# LCD_PWR.net
KiCad netlist of a schematic drawn in Altium Designer
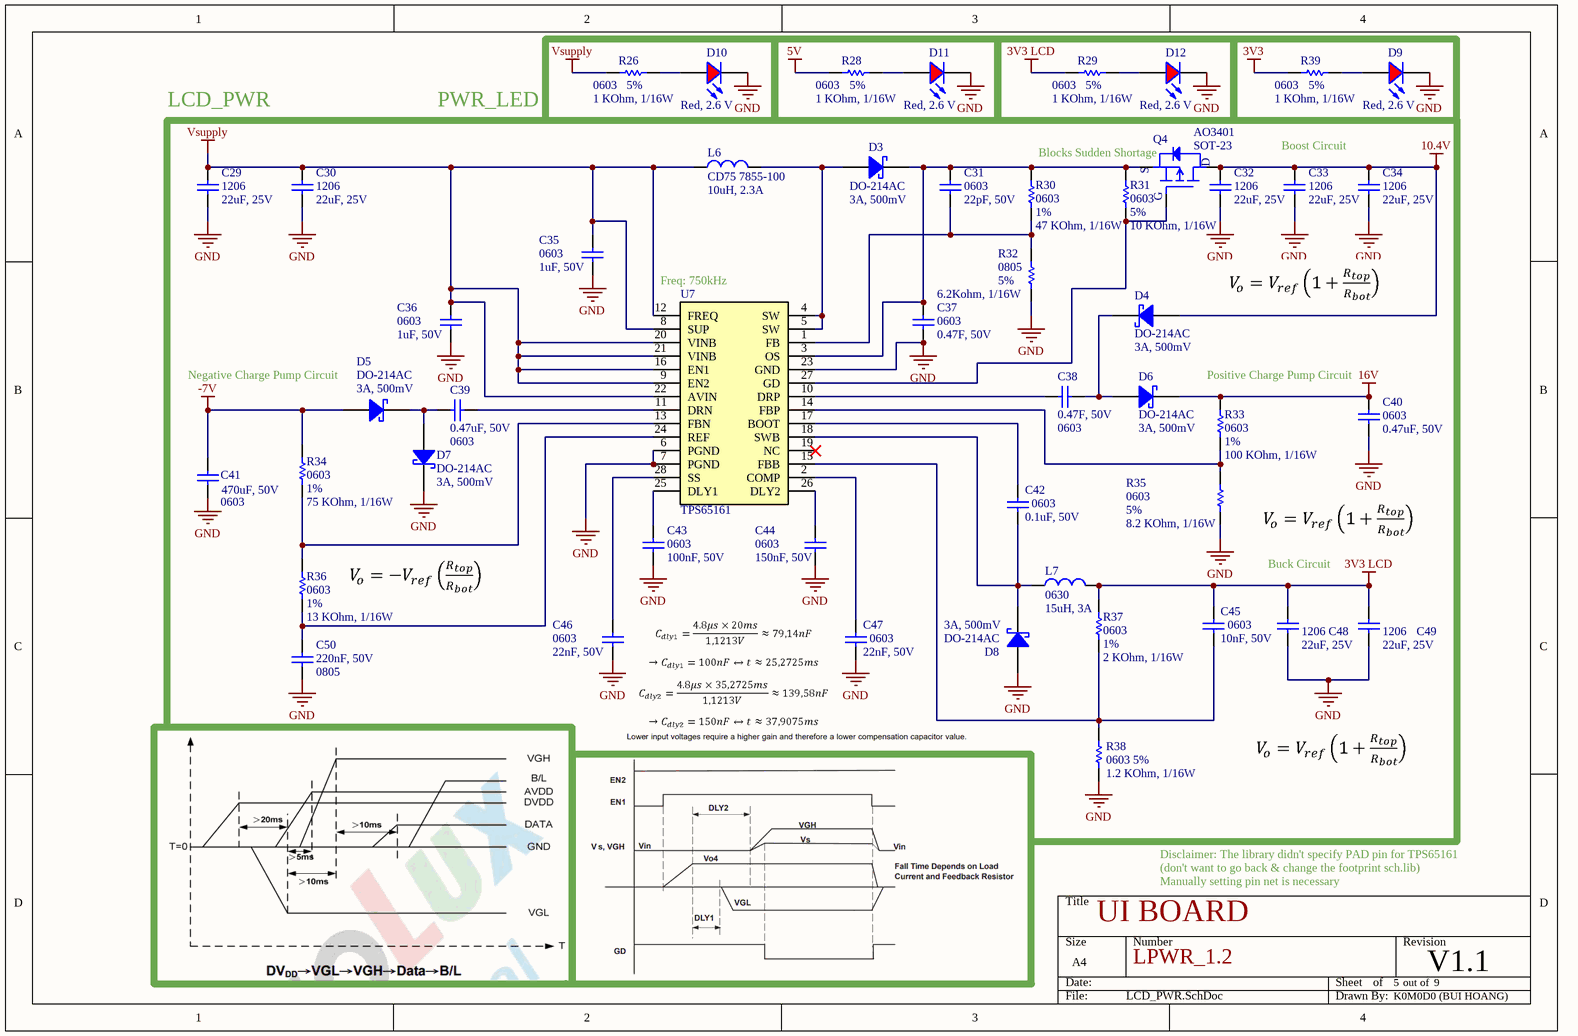
[diagram p0: LCD_PWR.SchDoc]

(export (version "E")
  (design (tool "Eeschema 10.0.6"))
  (components
    (comp (ref "C29")
      (value "22uF, 25V")
      (footprint "C_1206")
      (description "CAP_1206")
      (fields (field (name "PACKAGE") "1206"))
      (libsource (lib "DisplayLib") (part "CAP_1206"))
    )
    (comp (ref "C30")
      (value "22uF, 25V")
      (footprint "C_1206")
      (description "CAP_1206")
      (fields (field (name "PACKAGE") "1206"))
      (libsource (lib "DisplayLib") (part "CAP_1206"))
    )
    (comp (ref "C31")
      (value "22pF, 50V")
      (footprint "C_0603")
      (description "CAP_0603")
      (fields (field (name "PACKAGE") "0603"))
      (libsource (lib "DisplayLib") (part "CAP_0603"))
    )
    (comp (ref "C32")
      (value "22uF, 25V")
      (footprint "C_1206")
      (description "CAP_1206")
      (fields (field (name "PACKAGE") "1206"))
      (libsource (lib "DisplayLib") (part "CAP_1206"))
    )
    (comp (ref "C33")
      (value "22uF, 25V")
      (footprint "C_1206")
      (description "CAP_1206")
      (fields (field (name "PACKAGE") "1206"))
      (libsource (lib "DisplayLib") (part "CAP_1206"))
    )
    (comp (ref "C34")
      (value "22uF, 25V")
      (footprint "C_1206")
      (description "CAP_1206")
      (fields (field (name "PACKAGE") "1206"))
      (libsource (lib "DisplayLib") (part "CAP_1206"))
    )
    (comp (ref "C35")
      (value "1uF, 50V")
      (footprint "C_0603")
      (description "CAP_0603")
      (fields (field (name "PACKAGE") "0603"))
      (libsource (lib "DisplayLib") (part "CAP_0603"))
    )
    (comp (ref "C36")
      (value "1uF, 50V")
      (footprint "C_0603")
      (description "CAP_0603")
      (fields (field (name "PACKAGE") "0603"))
      (libsource (lib "DisplayLib") (part "CAP_0603"))
    )
    (comp (ref "C37")
      (value "0.47F, 50V")
      (footprint "C_0603")
      (description "CAP_0603")
      (fields (field (name "PACKAGE") "0603"))
      (libsource (lib "DisplayLib") (part "CAP_0603"))
    )
    (comp (ref "C38")
      (value "0.47F, 50V")
      (footprint "C_0603")
      (description "CAP_0603")
      (fields (field (name "PACKAGE") "0603"))
      (libsource (lib "DisplayLib") (part "CAP_0603"))
    )
    (comp (ref "C39")
      (value "0.47uF, 50V")
      (footprint "C_0603")
      (description "CAP_0603")
      (fields (field (name "PACKAGE") "0603"))
      (libsource (lib "DisplayLib") (part "CAP_0603"))
    )
    (comp (ref "C40")
      (value "0.47uF, 50V")
      (footprint "C_0603")
      (description "CAP_0603")
      (fields (field (name "PACKAGE") "0603"))
      (libsource (lib "DisplayLib") (part "CAP_0603"))
    )
    (comp (ref "C41")
      (value "470uF, 50V")
      (footprint "C_0603")
      (description "CAP_0603")
      (fields (field (name "PACKAGE") "0603"))
      (libsource (lib "DisplayLib") (part "CAP_0603"))
    )
    (comp (ref "C42")
      (value "0.1uF, 50V")
      (footprint "C_0603")
      (description "CAP_0603")
      (fields (field (name "PACKAGE") "0603"))
      (libsource (lib "DisplayLib") (part "CAP_0603"))
    )
    (comp (ref "C43")
      (value "100nF, 50V")
      (footprint "C_0603")
      (description "CAP_0603")
      (fields (field (name "PACKAGE") "0603"))
      (libsource (lib "DisplayLib") (part "CAP_0603"))
    )
    (comp (ref "C44")
      (value "150nF, 50V")
      (footprint "C_0603")
      (description "CAP_0603")
      (fields (field (name "PACKAGE") "0603"))
      (libsource (lib "DisplayLib") (part "CAP_0603"))
    )
    (comp (ref "C45")
      (value "10nF, 50V")
      (footprint "C_0603")
      (description "CAP_0603")
      (fields (field (name "PACKAGE") "0603"))
      (libsource (lib "DisplayLib") (part "CAP_0603"))
    )
    (comp (ref "C46")
      (value "22nF, 50V")
      (footprint "C_0603")
      (description "CAP_0603")
      (fields (field (name "PACKAGE") "0603"))
      (libsource (lib "DisplayLib") (part "CAP_0603"))
    )
    (comp (ref "C47")
      (value "22nF, 50V")
      (footprint "C_0603")
      (description "CAP_0603")
      (fields (field (name "PACKAGE") "0603"))
      (libsource (lib "DisplayLib") (part "CAP_0603"))
    )
    (comp (ref "C48")
      (value "22uF, 25V")
      (footprint "C_1206")
      (description "CAP_1206")
      (fields (field (name "PACKAGE") "1206"))
      (libsource (lib "DisplayLib") (part "CAP_1206"))
    )
    (comp (ref "C49")
      (value "22uF, 25V")
      (footprint "C_1206")
      (description "CAP_1206")
      (fields (field (name "PACKAGE") "1206"))
      (libsource (lib "DisplayLib") (part "CAP_1206"))
    )
    (comp (ref "C50")
      (value "220nF, 50V")
      (footprint "C_0805")
      (description "CAP_0805")
      (fields (field (name "PACKAGE") "0805"))
      (libsource (lib "DisplayLib") (part "CAP_0805"))
    )
    (comp (ref "D3")
      (value "3A, 500mV")
      (footprint "PKG_SMA (DO-214AC)")
      (description "SS34")
      (fields (field (name "PACKAGE") "DO-214AC"))
      (libsource (lib "DisplayLib") (part "SCHOTTKY"))
    )
    (comp (ref "D4")
      (value "3A, 500mV")
      (footprint "PKG_SMA (DO-214AC)")
      (description "SS34")
      (fields (field (name "PACKAGE") "DO-214AC"))
      (libsource (lib "DisplayLib") (part "SCHOTTKY"))
    )
    (comp (ref "D5")
      (value "3A, 500mV")
      (footprint "PKG_SMA (DO-214AC)")
      (description "SS34")
      (fields (field (name "PACKAGE") "DO-214AC"))
      (libsource (lib "DisplayLib") (part "SCHOTTKY"))
    )
    (comp (ref "D6")
      (value "3A, 500mV")
      (footprint "PKG_SMA (DO-214AC)")
      (description "SS34")
      (fields (field (name "PACKAGE") "DO-214AC"))
      (libsource (lib "DisplayLib") (part "SCHOTTKY"))
    )
    (comp (ref "D7")
      (value "3A, 500mV")
      (footprint "PKG_SMA (DO-214AC)")
      (description "SS34")
      (fields (field (name "PACKAGE") "DO-214AC"))
      (libsource (lib "DisplayLib") (part "SCHOTTKY"))
    )
    (comp (ref "D8")
      (value "3A, 500mV")
      (footprint "PKG_SMA (DO-214AC)")
      (description "SS34")
      (fields (field (name "PACKAGE") "DO-214AC"))
      (libsource (lib "DisplayLib") (part "SCHOTTKY"))
    )
    (comp (ref "D9")
      (value "Red, 2.6 V")
      (footprint "LED_1206")
      (description "Red LED")
      (libsource (lib "DisplayLib") (part "RED"))
    )
    (comp (ref "D10")
      (value "Red, 2.6 V")
      (footprint "LED_1206")
      (description "Red LED")
      (libsource (lib "DisplayLib") (part "RED"))
    )
    (comp (ref "D11")
      (value "Red, 2.6 V")
      (footprint "LED_1206")
      (description "Red LED")
      (libsource (lib "DisplayLib") (part "RED"))
    )
    (comp (ref "D12")
      (value "Red, 2.6 V")
      (footprint "LED_1206")
      (description "Red LED")
      (libsource (lib "DisplayLib") (part "RED"))
    )
    (comp (ref "L6")
      (value "10uH, 2.3A")
      (footprint "COIL_CDRH")
      (description "IN_CD104_100")
      (fields (field (name "PACKAGE") "CD75 7855-100"))
      (libsource (lib "DisplayLib") (part "IN_CD104_100"))
    )
    (comp (ref "L7")
      (value "15uH, 3A")
      (footprint "COIL_74")
      (description "IN_0630")
      (fields (field (name "PACKAGE") "0630"))
      (libsource (lib "DisplayLib") (part "IN_0630"))
    )
    (comp (ref "Q4")
      (value "AO3401")
      (footprint "PKG_SOT-23")
      (description "P-Channel 30 V 4A (Ta) 1.4W (Ta) Surface Mount SOT-23-3")
      (fields (field (name "PACKAGE") "SOT-23"))
      (libsource (lib "DisplayLib") (part "AO3401"))
    )
    (comp (ref "R26")
      (value "1 KOhm, 1/16W")
      (footprint "R_0603")
      (description "RES_0603")
      (fields (field (name "PACKAGE") "0603") (field (name "ACC") "5%"))
      (libsource (lib "DisplayLib") (part "RES_0603"))
    )
    (comp (ref "R28")
      (value "1 KOhm, 1/16W")
      (footprint "R_0603")
      (description "RES_0603")
      (fields (field (name "PACKAGE") "0603") (field (name "ACC") "5%"))
      (libsource (lib "DisplayLib") (part "RES_0603"))
    )
    (comp (ref "R29")
      (value "1 KOhm, 1/16W")
      (footprint "R_0603")
      (description "RES_0603")
      (fields (field (name "PACKAGE") "0603") (field (name "ACC") "5%"))
      (libsource (lib "DisplayLib") (part "RES_0603"))
    )
    (comp (ref "R30")
      (value "47 KOhm, 1/16W")
      (footprint "R_0603")
      (description "RES_0603")
      (fields (field (name "PACKAGE") "0603") (field (name "ACC") "1%"))
      (libsource (lib "DisplayLib") (part "RES_0603"))
    )
    (comp (ref "R31")
      (value "10 KOhm, 1/16W")
      (footprint "R_0603")
      (description "RES_0603")
      (fields (field (name "PACKAGE") "0603") (field (name "ACC") "5%"))
      (libsource (lib "DisplayLib") (part "RES_0603"))
    )
    (comp (ref "R32")
      (value "6.2Kohm, 1/16W")
      (footprint "R_0805")
      (description "RES_0805")
      (fields (field (name "PACKAGE") "0805") (field (name "ACC") "5%"))
      (libsource (lib "DisplayLib") (part "RES_0805"))
    )
    (comp (ref "R33")
      (value "100 KOhm, 1/16W")
      (footprint "R_0603")
      (description "RES_0603")
      (fields (field (name "PACKAGE") "0603") (field (name "ACC") "1%"))
      (libsource (lib "DisplayLib") (part "RES_0603"))
    )
    (comp (ref "R34")
      (value "75 KOhm, 1/16W")
      (footprint "R_0603")
      (description "RES_0603")
      (fields (field (name "PACKAGE") "0603") (field (name "ACC") "1%"))
      (libsource (lib "DisplayLib") (part "RES_0603"))
    )
    (comp (ref "R35")
      (value "8.2 KOhm, 1/16W")
      (footprint "R_0603")
      (description "RES_0603")
      (fields (field (name "PACKAGE") "0603") (field (name "ACC") "5%"))
      (libsource (lib "DisplayLib") (part "RES_0603"))
    )
    (comp (ref "R36")
      (value "13 KOhm, 1/16W")
      (footprint "R_0603")
      (description "RES_0603")
      (fields (field (name "PACKAGE") "0603") (field (name "ACC") "1%"))
      (libsource (lib "DisplayLib") (part "RES_0603"))
    )
    (comp (ref "R37")
      (value "2 KOhm, 1/16W")
      (footprint "R_0603")
      (description "RES_0603")
      (fields (field (name "PACKAGE") "0603") (field (name "ACC") "1%"))
      (libsource (lib "DisplayLib") (part "RES_0603"))
    )
    (comp (ref "R38")
      (value "1.2 KOhm, 1/16W")
      (footprint "R_0603")
      (description "RES_0603")
      (fields (field (name "PACKAGE") "0603") (field (name "ACC") "5%"))
      (libsource (lib "DisplayLib") (part "RES_0603"))
    )
    (comp (ref "R39")
      (value "1 KOhm, 1/16W")
      (footprint "R_0603")
      (description "RES_0603")
      (fields (field (name "PACKAGE") "0603") (field (name "ACC") "5%"))
      (libsource (lib "DisplayLib") (part "RES_0603"))
    )
    (comp (ref "U7")
      (value "TPS65161")
      (footprint "PKG_HTSSOP-28")
      (description "BIAS POWER SUPPLY FOR TV AND MONITOR TFT LCD PANELS")
      (libsource (lib "DisplayLib") (part "TPS65161"))
    )
  )
  (nets
    (net (code "1") (name "-7V") (class "Default")
      (node (ref "C41") (pin "1") (pinfunction "1_1") (pintype "passive"))
      (node (ref "D5") (pin "2") (pinfunction "A_2") (pintype "passive"))
      (node (ref "R34") (pin "2") (pinfunction "2_2") (pintype "passive"))
    )
    (net (code "2") (name "3V3") (class "Default")
      (node (ref "R39") (pin "1") (pinfunction "1_1") (pintype "passive"))
    )
    (net (code "3") (name "3V3 LCD") (class "Default")
      (node (ref "C45") (pin "2") (pinfunction "2_2") (pintype "passive"))
      (node (ref "C48") (pin "2") (pinfunction "2_2") (pintype "passive"))
      (node (ref "C49") (pin "2") (pinfunction "2_2") (pintype "passive"))
      (node (ref "L7") (pin "2") (pinfunction "2_2") (pintype "passive"))
      (node (ref "R29") (pin "1") (pinfunction "1_1") (pintype "passive"))
      (node (ref "R37") (pin "2") (pinfunction "2_2") (pintype "passive"))
    )
    (net (code "4") (name "5V") (class "Default")
      (node (ref "R28") (pin "1") (pinfunction "1_1") (pintype "passive"))
    )
    (net (code "5") (name "10.4V") (class "Default")
      (node (ref "C32") (pin "2") (pinfunction "2_2") (pintype "passive"))
      (node (ref "C33") (pin "2") (pinfunction "2_2") (pintype "passive"))
      (node (ref "C34") (pin "2") (pinfunction "2_2") (pintype "passive"))
      (node (ref "D4") (pin "2") (pinfunction "A_2") (pintype "passive"))
      (node (ref "Q4") (pin "3") (pinfunction "D_3") (pintype "passive"))
    )
    (net (code "6") (name "16V") (class "Default")
      (node (ref "C40") (pin "2") (pinfunction "2_2") (pintype "passive"))
      (node (ref "D6") (pin "1") (pinfunction "K_1") (pintype "passive"))
      (node (ref "R33") (pin "2") (pinfunction "2_2") (pintype "passive"))
    )
    (net (code "7") (name "GND") (class "Default")
      (node (ref "C29") (pin "1") (pinfunction "1_1") (pintype "passive"))
      (node (ref "C30") (pin "1") (pinfunction "1_1") (pintype "passive"))
      (node (ref "C32") (pin "1") (pinfunction "1_1") (pintype "passive"))
      (node (ref "C33") (pin "1") (pinfunction "1_1") (pintype "passive"))
      (node (ref "C34") (pin "1") (pinfunction "1_1") (pintype "passive"))
      (node (ref "C35") (pin "1") (pinfunction "1_1") (pintype "passive"))
      (node (ref "C36") (pin "1") (pinfunction "1_1") (pintype "passive"))
      (node (ref "C37") (pin "1") (pinfunction "1_1") (pintype "passive"))
      (node (ref "C40") (pin "1") (pinfunction "1_1") (pintype "passive"))
      (node (ref "C41") (pin "2") (pinfunction "2_2") (pintype "passive"))
      (node (ref "C43") (pin "1") (pinfunction "1_1") (pintype "passive"))
      (node (ref "C44") (pin "1") (pinfunction "1_1") (pintype "passive"))
      (node (ref "C46") (pin "1") (pinfunction "1_1") (pintype "passive"))
      (node (ref "C47") (pin "1") (pinfunction "1_1") (pintype "passive"))
      (node (ref "C48") (pin "1") (pinfunction "1_1") (pintype "passive"))
      (node (ref "C49") (pin "1") (pinfunction "1_1") (pintype "passive"))
      (node (ref "C50") (pin "2") (pinfunction "2_2") (pintype "passive"))
      (node (ref "D10") (pin "1") (pinfunction "K_1") (pintype "passive"))
      (node (ref "D11") (pin "1") (pinfunction "K_1") (pintype "passive"))
      (node (ref "D12") (pin "1") (pinfunction "K_1") (pintype "passive"))
      (node (ref "D7") (pin "1") (pinfunction "K_1") (pintype "passive"))
      (node (ref "D8") (pin "2") (pinfunction "A_2") (pintype "passive"))
      (node (ref "D9") (pin "1") (pinfunction "K_1") (pintype "passive"))
      (node (ref "R32") (pin "1") (pinfunction "1_1") (pintype "passive"))
      (node (ref "R35") (pin "1") (pinfunction "1_1") (pintype "passive"))
      (node (ref "R38") (pin "1") (pinfunction "1_1") (pintype "passive"))
      (node (ref "U7") (pin "23") (pinfunction "GND_23") (pintype "passive"))
      (node (ref "U7") (pin "6") (pinfunction "PGND_6") (pintype "passive"))
      (node (ref "U7") (pin "7") (pinfunction "PGND_7") (pintype "passive"))
    )
    (net (code "8") (name "Net-(D3-A)") (class "Default")
      (node (ref "D3") (pin "2") (pinfunction "A_2") (pintype "passive"))
      (node (ref "L6") (pin "2") (pinfunction "2_2") (pintype "passive"))
      (node (ref "U7") (pin "4") (pinfunction "SW_4") (pintype "passive"))
      (node (ref "U7") (pin "5") (pinfunction "SW_5") (pintype "passive"))
    )
    (net (code "9") (name "Net-(D3-K)") (class "Default")
      (node (ref "C31") (pin "2") (pinfunction "2_2") (pintype "passive"))
      (node (ref "C37") (pin "2") (pinfunction "2_2") (pintype "passive"))
      (node (ref "D3") (pin "1") (pinfunction "K_1") (pintype "passive"))
      (node (ref "Q4") (pin "2") (pinfunction "S_2") (pintype "passive"))
      (node (ref "R30") (pin "2") (pinfunction "2_2") (pintype "passive"))
      (node (ref "R31") (pin "2") (pinfunction "2_2") (pintype "passive"))
      (node (ref "U7") (pin "3") (pinfunction "OS_3") (pintype "passive"))
    )
    (net (code "10") (name "Net-(D4-K)") (class "Default")
      (node (ref "C38") (pin "1") (pinfunction "1_1") (pintype "passive"))
      (node (ref "D4") (pin "1") (pinfunction "K_1") (pintype "passive"))
      (node (ref "D6") (pin "2") (pinfunction "A_2") (pintype "passive"))
    )
    (net (code "11") (name "Net-(D5-K)") (class "Default")
      (node (ref "C39") (pin "2") (pinfunction "2_2") (pintype "passive"))
      (node (ref "D5") (pin "1") (pinfunction "K_1") (pintype "passive"))
      (node (ref "D7") (pin "2") (pinfunction "A_2") (pintype "passive"))
    )
    (net (code "12") (name "Net-(D8-K)") (class "Default")
      (node (ref "C42") (pin "1") (pinfunction "1_1") (pintype "passive"))
      (node (ref "D8") (pin "1") (pinfunction "K_1") (pintype "passive"))
      (node (ref "L7") (pin "1") (pinfunction "1_1") (pintype "passive"))
      (node (ref "U7") (pin "18") (pinfunction "SWB_18") (pintype "passive"))
    )
    (net (code "13") (name "Net-(D9-A)") (class "Default")
      (node (ref "D9") (pin "2") (pinfunction "A_2") (pintype "passive"))
      (node (ref "R39") (pin "2") (pinfunction "2_2") (pintype "passive"))
    )
    (net (code "14") (name "Net-(D10-A)") (class "Default")
      (node (ref "D10") (pin "2") (pinfunction "A_2") (pintype "passive"))
      (node (ref "R26") (pin "2") (pinfunction "2_2") (pintype "passive"))
    )
    (net (code "15") (name "Net-(D11-A)") (class "Default")
      (node (ref "D11") (pin "2") (pinfunction "A_2") (pintype "passive"))
      (node (ref "R28") (pin "2") (pinfunction "2_2") (pintype "passive"))
    )
    (net (code "16") (name "Net-(D12-A)") (class "Default")
      (node (ref "D12") (pin "2") (pinfunction "A_2") (pintype "passive"))
      (node (ref "R29") (pin "2") (pinfunction "2_2") (pintype "passive"))
    )
    (net (code "17") (name "Net-(Q4-G)") (class "Default")
      (node (ref "Q4") (pin "1") (pinfunction "G_1") (pintype "passive"))
      (node (ref "R31") (pin "1") (pinfunction "1_1") (pintype "passive"))
      (node (ref "U7") (pin "27") (pinfunction "GD_27") (pintype "passive"))
    )
    (net (code "18") (name "Net-(U7-BOOT)") (class "Default")
      (node (ref "C42") (pin "2") (pinfunction "2_2") (pintype "passive"))
      (node (ref "U7") (pin "17") (pinfunction "BOOT_17") (pintype "passive"))
    )
    (net (code "19") (name "Net-(U7-COMP)") (class "Default")
      (node (ref "C47") (pin "2") (pinfunction "2_2") (pintype "passive"))
      (node (ref "U7") (pin "2") (pinfunction "COMP_2") (pintype "passive"))
    )
    (net (code "20") (name "Net-(U7-DLY1)") (class "Default")
      (node (ref "C43") (pin "2") (pinfunction "2_2") (pintype "passive"))
      (node (ref "U7") (pin "25") (pinfunction "DLY1_25") (pintype "passive"))
    )
    (net (code "21") (name "Net-(U7-DLY2)") (class "Default")
      (node (ref "C44") (pin "2") (pinfunction "2_2") (pintype "passive"))
      (node (ref "U7") (pin "26") (pinfunction "DLY2_26") (pintype "passive"))
    )
    (net (code "22") (name "Net-(U7-DRN)") (class "Default")
      (node (ref "C39") (pin "1") (pinfunction "1_1") (pintype "passive"))
      (node (ref "U7") (pin "11") (pinfunction "DRN_11") (pintype "passive"))
    )
    (net (code "23") (name "Net-(U7-DRP)") (class "Default")
      (node (ref "C38") (pin "2") (pinfunction "2_2") (pintype "passive"))
      (node (ref "U7") (pin "10") (pinfunction "DRP_10") (pintype "passive"))
    )
    (net (code "24") (name "Net-(U7-FB)") (class "Default")
      (node (ref "C31") (pin "1") (pinfunction "1_1") (pintype "passive"))
      (node (ref "R30") (pin "1") (pinfunction "1_1") (pintype "passive"))
      (node (ref "R32") (pin "2") (pinfunction "2_2") (pintype "passive"))
      (node (ref "U7") (pin "1") (pinfunction "FB_1") (pintype "passive"))
    )
    (net (code "25") (name "Net-(U7-FBB)") (class "Default")
      (node (ref "C45") (pin "1") (pinfunction "1_1") (pintype "passive"))
      (node (ref "R37") (pin "1") (pinfunction "1_1") (pintype "passive"))
      (node (ref "R38") (pin "2") (pinfunction "2_2") (pintype "passive"))
      (node (ref "U7") (pin "15") (pinfunction "FBB_15") (pintype "passive"))
    )
    (net (code "26") (name "Net-(U7-FBN)") (class "Default")
      (node (ref "R34") (pin "1") (pinfunction "1_1") (pintype "passive"))
      (node (ref "R36") (pin "2") (pinfunction "2_2") (pintype "passive"))
      (node (ref "U7") (pin "13") (pinfunction "FBN_13") (pintype "passive"))
    )
    (net (code "27") (name "Net-(U7-FBP)") (class "Default")
      (node (ref "R33") (pin "1") (pinfunction "1_1") (pintype "passive"))
      (node (ref "R35") (pin "2") (pinfunction "2_2") (pintype "passive"))
      (node (ref "U7") (pin "14") (pinfunction "FBP_14") (pintype "passive"))
    )
    (net (code "28") (name "Net-(U7-REF)") (class "Default")
      (node (ref "C50") (pin "1") (pinfunction "1_1") (pintype "passive"))
      (node (ref "R36") (pin "1") (pinfunction "1_1") (pintype "passive"))
      (node (ref "U7") (pin "24") (pinfunction "REF_24") (pintype "passive"))
    )
    (net (code "29") (name "Net-(U7-SS)") (class "Default")
      (node (ref "C46") (pin "2") (pinfunction "2_2") (pintype "passive"))
      (node (ref "U7") (pin "28") (pinfunction "SS_28") (pintype "passive"))
    )
    (net (code "30") (name "Vsupply") (class "Default")
      (node (ref "C29") (pin "2") (pinfunction "2_2") (pintype "passive"))
      (node (ref "C30") (pin "2") (pinfunction "2_2") (pintype "passive"))
      (node (ref "C35") (pin "2") (pinfunction "2_2") (pintype "passive"))
      (node (ref "C36") (pin "2") (pinfunction "2_2") (pintype "passive"))
      (node (ref "L6") (pin "1") (pinfunction "1_1") (pintype "passive"))
      (node (ref "R26") (pin "1") (pinfunction "1_1") (pintype "passive"))
      (node (ref "U7") (pin "12") (pinfunction "FREQ_12") (pintype "passive"))
      (node (ref "U7") (pin "16") (pinfunction "EN1_16") (pintype "passive"))
      (node (ref "U7") (pin "20") (pinfunction "VINB_20") (pintype "passive"))
      (node (ref "U7") (pin "21") (pinfunction "VINB_21") (pintype "passive"))
      (node (ref "U7") (pin "22") (pinfunction "AVIN_22") (pintype "passive"))
      (node (ref "U7") (pin "8") (pinfunction "SUP_8") (pintype "passive"))
      (node (ref "U7") (pin "9") (pinfunction "EN2_9") (pintype "passive"))
    )
    (net (code "31") (name "unconnected-(U7-NC-Pad19)") (class "Default")
      (node (ref "U7") (pin "19") (pinfunction "NC_19") (pintype "passive+no_connect"))
    )
  )
)
